# realy_wifi_obd.net
KiCad netlist of a schematic drawn in EAGLE
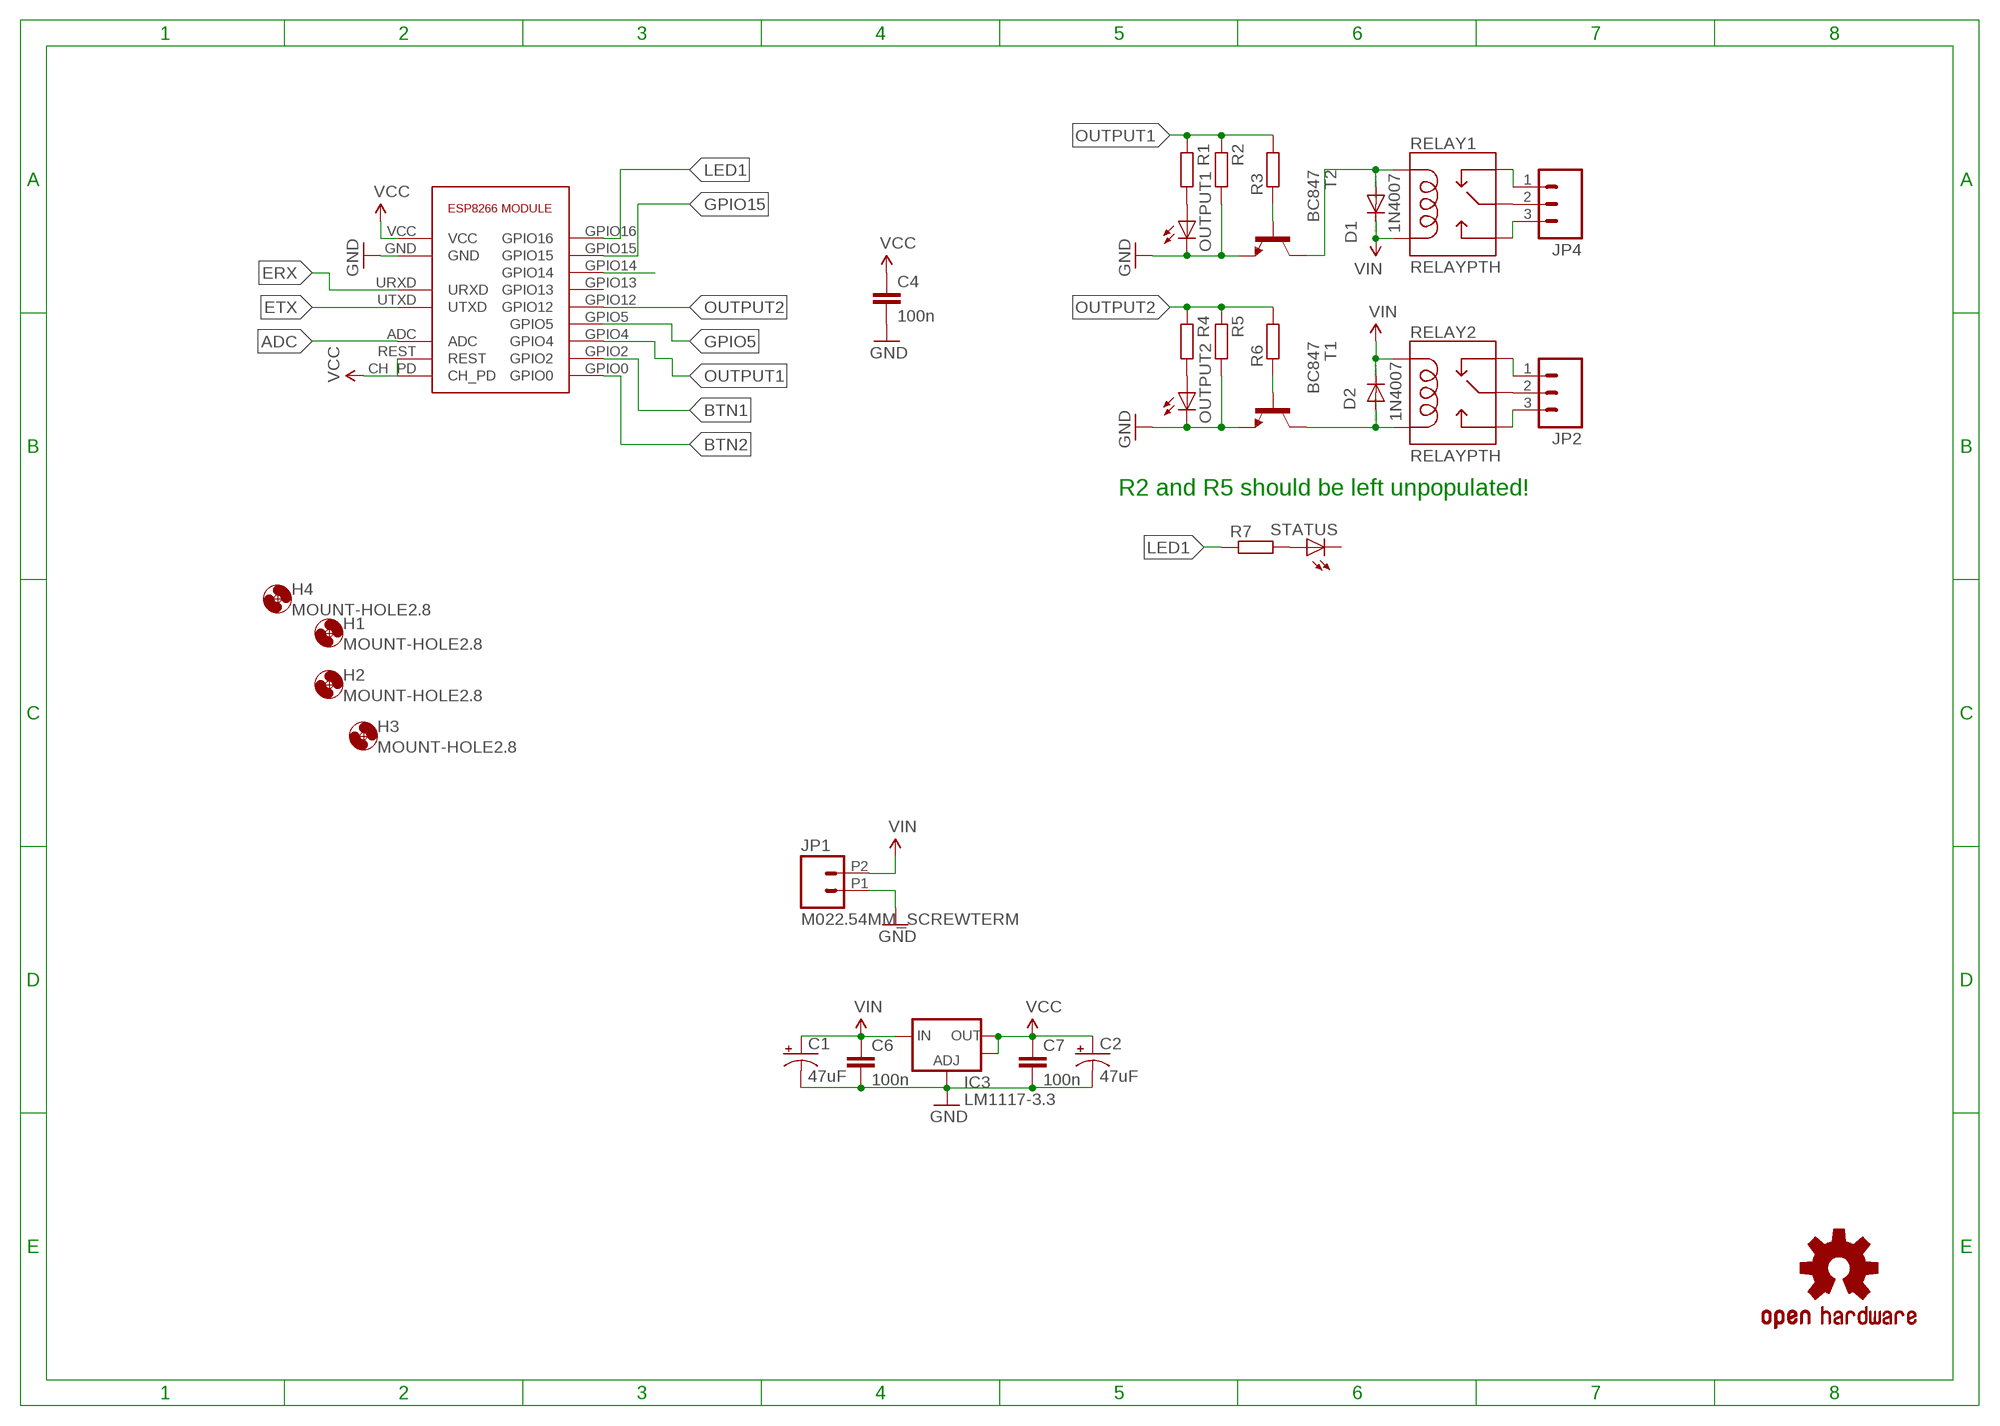
[diagram p0: schematic, sheet 1]

(export (version "E")
  (design (tool "Eeschema 10.0.6"))
  (components
    (comp (ref "C1")
      (value "47uF")
      (footprint "eagle-import:PANASONIC_D")
      (libsource (lib "eagle-import") (part "CAP_POLD"))
    )
    (comp (ref "C2")
      (value "47uF")
      (footprint "eagle-import:PANASONIC_D")
      (libsource (lib "eagle-import") (part "CAP_POLD"))
    )
    (comp (ref "C4")
      (value "100n")
      (footprint "eagle-import:C0805K")
      (libsource (lib "eagle-import") (part "C-EUC0805K"))
    )
    (comp (ref "C6")
      (value "100n")
      (footprint "eagle-import:C0805K")
      (libsource (lib "eagle-import") (part "C-EUC0805K"))
    )
    (comp (ref "C7")
      (value "100n")
      (footprint "eagle-import:C0805K")
      (libsource (lib "eagle-import") (part "C-EUC0805K"))
    )
    (comp (ref "D1")
      (value "1N4942")
      (footprint "eagle-import:DO41-10")
      (libsource (lib "eagle-import") (part "1N4942"))
    )
    (comp (ref "D2")
      (value "1N4942")
      (footprint "eagle-import:DO41-10")
      (libsource (lib "eagle-import") (part "1N4942"))
    )
    (comp (ref "ESP8266")
      (value "ESP8266ESP-07")
      (footprint "eagle-import:ESP-12")
      (libsource (lib "eagle-import") (part "ESP8266ESP-07"))
    )
    (comp (ref "H1")
      (value "MOUNT-HOLE2.8")
      (footprint "eagle-import:2,8")
      (libsource (lib "eagle-import") (part "MOUNT-HOLE2.8"))
    )
    (comp (ref "H2")
      (value "MOUNT-HOLE2.8")
      (footprint "eagle-import:2,8")
      (libsource (lib "eagle-import") (part "MOUNT-HOLE2.8"))
    )
    (comp (ref "H3")
      (value "MOUNT-HOLE2.8")
      (footprint "eagle-import:2,8")
      (libsource (lib "eagle-import") (part "MOUNT-HOLE2.8"))
    )
    (comp (ref "H4")
      (value "MOUNT-HOLE2.8")
      (footprint "eagle-import:2,8")
      (libsource (lib "eagle-import") (part "MOUNT-HOLE2.8"))
    )
    (comp (ref "IC3")
      (value "LM1117-3.3")
      (footprint "eagle-import:SOT223")
      (libsource (lib "eagle-import") (part "V_REG_LM1117SOT223"))
    )
    (comp (ref "JP1")
      (value "M022.54MM_SCREWTERM")
      (footprint "eagle-import:1X02_2.54_SCREWTERM")
      (libsource (lib "eagle-import") (part "M022.54MM_SCREWTERM"))
    )
    (comp (ref "JP2")
      (value "M03-SCREW-5MM")
      (footprint "eagle-import:SCREWTERMINAL-5MM-3")
      (libsource (lib "eagle-import") (part "M03-SCREW-5MM"))
    )
    (comp (ref "JP4")
      (value "M03-SCREW-5MM")
      (footprint "eagle-import:SCREWTERMINAL-5MM-3")
      (libsource (lib "eagle-import") (part "M03-SCREW-5MM"))
    )
    (comp (ref "LOGO1")
      (value "OSHW-LOGOL")
      (footprint "eagle-import:OSHW-LOGO-L")
      (libsource (lib "eagle-import") (part "OSHW-LOGOL"))
    )
    (comp (ref "OUTPUT1")
      (value "LEDCHIP-LED0805")
      (footprint "eagle-import:CHIP-LED0805")
      (libsource (lib "eagle-import") (part "LEDCHIP-LED0805"))
    )
    (comp (ref "OUTPUT2")
      (value "LEDCHIP-LED0805")
      (footprint "eagle-import:CHIP-LED0805")
      (libsource (lib "eagle-import") (part "LEDCHIP-LED0805"))
    )
    (comp (ref "R1")
      (value "SMARTPRJ_R-EU_M0805")
      (footprint "eagle-import:SMARTPRJ_M0805")
      (libsource (lib "eagle-import") (part "SMARTPRJ_R-EU_M0805"))
    )
    (comp (ref "R2")
      (value "SMARTPRJ_R-EU_M0805")
      (footprint "eagle-import:SMARTPRJ_M0805")
      (libsource (lib "eagle-import") (part "SMARTPRJ_R-EU_M0805"))
    )
    (comp (ref "R3")
      (value "SMARTPRJ_R-EU_M0805")
      (footprint "eagle-import:SMARTPRJ_M0805")
      (libsource (lib "eagle-import") (part "SMARTPRJ_R-EU_M0805"))
    )
    (comp (ref "R4")
      (value "SMARTPRJ_R-EU_M0805")
      (footprint "eagle-import:SMARTPRJ_M0805")
      (libsource (lib "eagle-import") (part "SMARTPRJ_R-EU_M0805"))
    )
    (comp (ref "R5")
      (value "SMARTPRJ_R-EU_M0805")
      (footprint "eagle-import:SMARTPRJ_M0805")
      (libsource (lib "eagle-import") (part "SMARTPRJ_R-EU_M0805"))
    )
    (comp (ref "R6")
      (value "SMARTPRJ_R-EU_M0805")
      (footprint "eagle-import:SMARTPRJ_M0805")
      (libsource (lib "eagle-import") (part "SMARTPRJ_R-EU_M0805"))
    )
    (comp (ref "R7")
      (value "SMARTPRJ_R-EU_M0805")
      (footprint "eagle-import:SMARTPRJ_M0805")
      (libsource (lib "eagle-import") (part "SMARTPRJ_R-EU_M0805"))
    )
    (comp (ref "RELAY1")
      (value "RELAYPTH")
      (footprint "eagle-import:SRD-05VDC-SL-C")
      (libsource (lib "eagle-import") (part "RELAYPTH"))
    )
    (comp (ref "RELAY2")
      (value "RELAYPTH")
      (footprint "eagle-import:SRD-05VDC-SL-C")
      (libsource (lib "eagle-import") (part "RELAYPTH"))
    )
    (comp (ref "STATUS")
      (value "LEDCHIP-LED0805")
      (footprint "eagle-import:CHIP-LED0805")
      (libsource (lib "eagle-import") (part "LEDCHIP-LED0805"))
    )
    (comp (ref "T1")
      (value "BC847")
      (footprint "eagle-import:SOT23")
      (libsource (lib "eagle-import") (part "BC847"))
    )
    (comp (ref "T2")
      (value "BC847")
      (footprint "eagle-import:SOT23")
      (libsource (lib "eagle-import") (part "BC847"))
    )
  )
  (nets
    (net (code "1") (name "ADC") (class "Default")
      (node (ref "ESP8266") (pin "ADC") (pinfunction "ADC_ADC") (pintype "bidirectional"))
    )
    (net (code "2") (name "BTN1") (class "Default")
      (node (ref "ESP8266") (pin "GPIO2") (pinfunction "GPIO2_GPIO2") (pintype "bidirectional"))
    )
    (net (code "3") (name "BTN2") (class "Default")
      (node (ref "ESP8266") (pin "GPIO0") (pinfunction "GPIO0_GPIO0") (pintype "bidirectional"))
    )
    (net (code "4") (name "ERX") (class "Default")
      (node (ref "ESP8266") (pin "URXD") (pinfunction "URXD_URXD") (pintype "input"))
    )
    (net (code "5") (name "ETX") (class "Default")
      (node (ref "ESP8266") (pin "UTXD") (pinfunction "UTXD_UTXD") (pintype "output"))
    )
    (net (code "6") (name "GND") (class "Default")
      (node (ref "C1") (pin "-") (pinfunction "-_-") (pintype "passive"))
      (node (ref "C2") (pin "-") (pinfunction "-_-") (pintype "passive"))
      (node (ref "C4") (pin "2") (pinfunction "2_2") (pintype "passive"))
      (node (ref "C6") (pin "2") (pinfunction "2_2") (pintype "passive"))
      (node (ref "C7") (pin "2") (pinfunction "2_2") (pintype "passive"))
      (node (ref "ESP8266") (pin "GND") (pinfunction "GND_GND") (pintype "power_in"))
      (node (ref "IC3") (pin "1") (pinfunction "ADJ_1") (pintype "input"))
      (node (ref "JP1") (pin "P1") (pinfunction "1_P1") (pintype "passive"))
      (node (ref "OUTPUT1") (pin "C") (pinfunction "C_C") (pintype "passive"))
      (node (ref "OUTPUT2") (pin "C") (pinfunction "C_C") (pintype "passive"))
      (node (ref "R2") (pin "2") (pinfunction "2_2") (pintype "passive"))
      (node (ref "R5") (pin "2") (pinfunction "2_2") (pintype "passive"))
      (node (ref "T1") (pin "2") (pinfunction "E_2") (pintype "passive"))
      (node (ref "T2") (pin "2") (pinfunction "E_2") (pintype "passive"))
    )
    (net (code "7") (name "GPIO5") (class "Default")
      (node (ref "ESP8266") (pin "GPIO5") (pinfunction "GPIO5_GPIO5") (pintype "bidirectional"))
    )
    (net (code "8") (name "GPIO15") (class "Default")
      (node (ref "ESP8266") (pin "GPIO15") (pinfunction "GPIO15_GPIO15") (pintype "bidirectional"))
    )
    (net (code "9") (name "LED1") (class "Default")
      (node (ref "ESP8266") (pin "GPIO16") (pinfunction "GPIO16_GPIO16") (pintype "bidirectional"))
      (node (ref "R7") (pin "1") (pinfunction "1_1") (pintype "passive"))
    )
    (net (code "10") (name "Net-(JP2-Pad2)") (class "Default")
      (node (ref "JP2") (pin "2") (pinfunction "2_2") (pintype "passive"))
      (node (ref "RELAY2") (pin "SWCOMMON") (pinfunction "SWCOMMON_SWCOMMON") (pintype "bidirectional"))
    )
    (net (code "11") (name "Net-(JP2-Pad3)") (class "Default")
      (node (ref "JP2") (pin "3") (pinfunction "3_3") (pintype "passive"))
      (node (ref "RELAY2") (pin "SWOPEN") (pinfunction "SWOPEN_SWOPEN") (pintype "bidirectional"))
    )
    (net (code "12") (name "Net-(JP4-Pad2)") (class "Default")
      (node (ref "JP4") (pin "2") (pinfunction "2_2") (pintype "passive"))
      (node (ref "RELAY1") (pin "SWCOMMON") (pinfunction "SWCOMMON_SWCOMMON") (pintype "bidirectional"))
    )
    (net (code "13") (name "Net-(JP4-Pad3)") (class "Default")
      (node (ref "JP4") (pin "3") (pinfunction "3_3") (pintype "passive"))
      (node (ref "RELAY1") (pin "SWOPEN") (pinfunction "SWOPEN_SWOPEN") (pintype "bidirectional"))
    )
    (net (code "14") (name "Net-(OUTPUT1-PadA)") (class "Default")
      (node (ref "OUTPUT1") (pin "A") (pinfunction "A_A") (pintype "passive"))
      (node (ref "R1") (pin "2") (pinfunction "2_2") (pintype "passive"))
    )
    (net (code "15") (name "Net-(OUTPUT2-PadA)") (class "Default")
      (node (ref "OUTPUT2") (pin "A") (pinfunction "A_A") (pintype "passive"))
      (node (ref "R4") (pin "2") (pinfunction "2_2") (pintype "passive"))
    )
    (net (code "16") (name "Net-(R7-Pad2)") (class "Default")
      (node (ref "R7") (pin "2") (pinfunction "2_2") (pintype "passive"))
      (node (ref "STATUS") (pin "A") (pinfunction "A_A") (pintype "passive"))
    )
    (net (code "17") (name "Net-(RELAY1-SWCLOSE)") (class "Default")
      (node (ref "JP4") (pin "1") (pinfunction "1_1") (pintype "passive"))
      (node (ref "RELAY1") (pin "SWCLOSED") (pinfunction "SWCLOSE_SWCLOSED") (pintype "bidirectional"))
    )
    (net (code "18") (name "Net-(RELAY2-SWCLOSE)") (class "Default")
      (node (ref "JP2") (pin "1") (pinfunction "1_1") (pintype "passive"))
      (node (ref "RELAY2") (pin "SWCLOSED") (pinfunction "SWCLOSE_SWCLOSED") (pintype "bidirectional"))
    )
    (net (code "19") (name "Net-(T1-B)") (class "Default")
      (node (ref "R6") (pin "1") (pinfunction "1_1") (pintype "passive"))
      (node (ref "T1") (pin "1") (pinfunction "B_1") (pintype "passive"))
    )
    (net (code "20") (name "Net-(T1-C)") (class "Default")
      (node (ref "D2") (pin "A") (pinfunction "A_A") (pintype "passive"))
      (node (ref "RELAY2") (pin "COIL0") (pinfunction "COIL0_COIL0") (pintype "bidirectional"))
      (node (ref "T1") (pin "3") (pinfunction "C_3") (pintype "passive"))
    )
    (net (code "21") (name "Net-(T2-B)") (class "Default")
      (node (ref "R3") (pin "1") (pinfunction "1_1") (pintype "passive"))
      (node (ref "T2") (pin "1") (pinfunction "B_1") (pintype "passive"))
    )
    (net (code "22") (name "Net-(T2-C)") (class "Default")
      (node (ref "D1") (pin "A") (pinfunction "A_A") (pintype "passive"))
      (node (ref "RELAY1") (pin "COIL1") (pinfunction "COIL1_COIL1") (pintype "bidirectional"))
      (node (ref "T2") (pin "3") (pinfunction "C_3") (pintype "passive"))
    )
    (net (code "23") (name "OUTPUT1") (class "Default")
      (node (ref "ESP8266") (pin "GPIO4") (pinfunction "GPIO4_GPIO4") (pintype "bidirectional"))
      (node (ref "R1") (pin "1") (pinfunction "1_1") (pintype "passive"))
      (node (ref "R2") (pin "1") (pinfunction "1_1") (pintype "passive"))
      (node (ref "R3") (pin "2") (pinfunction "2_2") (pintype "passive"))
    )
    (net (code "24") (name "OUTPUT2") (class "Default")
      (node (ref "ESP8266") (pin "GPIO12") (pinfunction "GPIO12_GPIO12") (pintype "bidirectional"))
      (node (ref "R4") (pin "1") (pinfunction "1_1") (pintype "passive"))
      (node (ref "R5") (pin "1") (pinfunction "1_1") (pintype "passive"))
      (node (ref "R6") (pin "2") (pinfunction "2_2") (pintype "passive"))
    )
    (net (code "25") (name "VCC") (class "Default")
      (node (ref "C2") (pin "+") (pinfunction "+_+") (pintype "passive"))
      (node (ref "C4") (pin "1") (pinfunction "1_1") (pintype "passive"))
      (node (ref "C7") (pin "1") (pinfunction "1_1") (pintype "passive"))
      (node (ref "ESP8266") (pin "CH_PD") (pinfunction "CH_PD_CH_PD") (pintype "bidirectional"))
      (node (ref "ESP8266") (pin "REST") (pinfunction "REST_REST") (pintype "bidirectional"))
      (node (ref "ESP8266") (pin "VCC") (pinfunction "VCC_VCC") (pintype "power_in"))
      (node (ref "IC3") (pin "2") (pinfunction "OUT_2") (pintype "output"))
      (node (ref "IC3") (pin "4") (pinfunction "OUT_4") (pintype "output"))
    )
    (net (code "26") (name "VIN") (class "Default")
      (node (ref "C1") (pin "+") (pinfunction "+_+") (pintype "passive"))
      (node (ref "C6") (pin "1") (pinfunction "1_1") (pintype "passive"))
      (node (ref "D1") (pin "C") (pinfunction "C_C") (pintype "passive"))
      (node (ref "D2") (pin "C") (pinfunction "C_C") (pintype "passive"))
      (node (ref "IC3") (pin "3") (pinfunction "IN_3") (pintype "input"))
      (node (ref "JP1") (pin "P2") (pinfunction "2_P2") (pintype "passive"))
      (node (ref "RELAY1") (pin "COIL0") (pinfunction "COIL0_COIL0") (pintype "bidirectional"))
      (node (ref "RELAY2") (pin "COIL1") (pinfunction "COIL1_COIL1") (pintype "bidirectional"))
    )
    (net (code "27") (name "unconnected-(ESP8266-PadGPIO13)") (class "Default")
      (node (ref "ESP8266") (pin "GPIO13") (pinfunction "GPIO13_GPIO13") (pintype "bidirectional"))
    )
    (net (code "28") (name "unconnected-(ESP8266-PadGPIO14)") (class "Default")
      (node (ref "ESP8266") (pin "GPIO14") (pinfunction "GPIO14_GPIO14") (pintype "bidirectional"))
    )
    (net (code "29") (name "unconnected-(STATUS-PadC)") (class "Default")
      (node (ref "STATUS") (pin "C") (pinfunction "C_C") (pintype "passive"))
    )
  )
)
